# SAI_IO_BOTTOM_PCB_BOARD.net
KiCad netlist of a schematic drawn in EAGLE
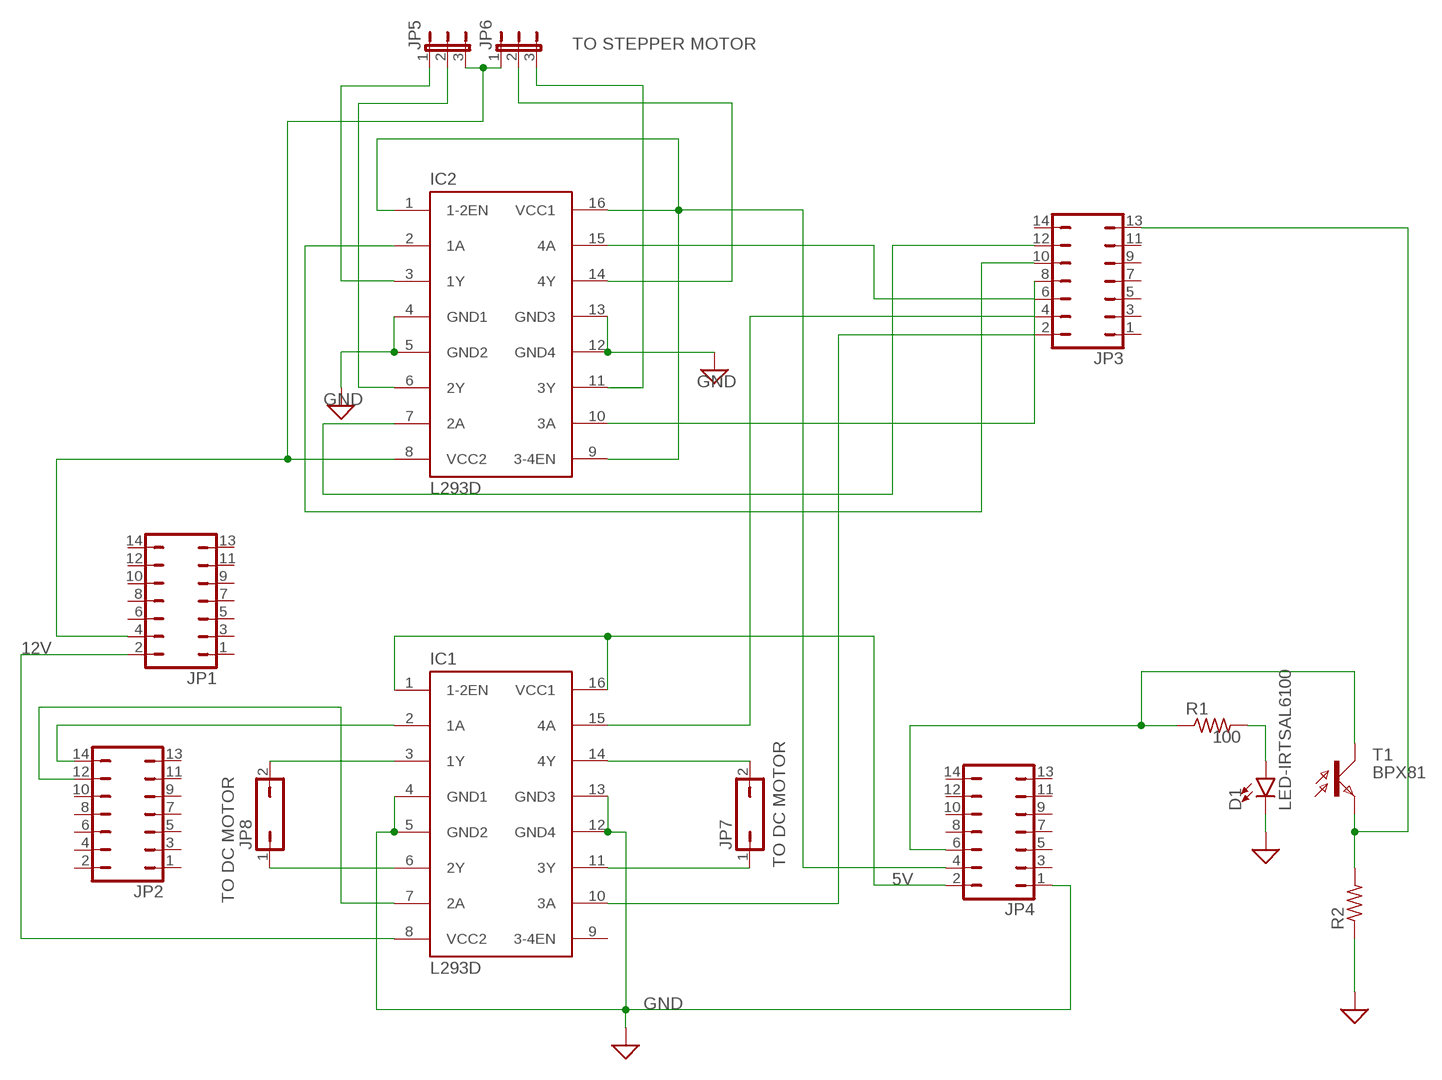
[diagram p0: schematic, sheet 1]

(export (version "E")
  (design (tool "Eeschema 10.0.6"))
  (components
    (comp (ref "D1")
      (value "LED-IRTSAL6100")
      (footprint "eagle-import:LED_5MM")
      (libsource (lib "eagle-import") (part "LED-IRTSAL6100"))
    )
    (comp (ref "IC1")
      (value "L293D")
      (footprint "eagle-import:DIL16")
      (libsource (lib "eagle-import") (part "L293D"))
    )
    (comp (ref "IC2")
      (value "L293D")
      (footprint "eagle-import:DIL16")
      (libsource (lib "eagle-import") (part "L293D"))
    )
    (comp (ref "JP1")
      (value "JP7Q")
      (footprint "eagle-import:JP7Q")
      (libsource (lib "eagle-import") (part "JP7Q"))
    )
    (comp (ref "JP2")
      (value "JP7Q")
      (footprint "eagle-import:JP7Q")
      (libsource (lib "eagle-import") (part "JP7Q"))
    )
    (comp (ref "JP3")
      (value "JP7Q")
      (footprint "eagle-import:JP7Q")
      (libsource (lib "eagle-import") (part "JP7Q"))
    )
    (comp (ref "JP4")
      (value "JP7Q")
      (footprint "eagle-import:JP7Q")
      (libsource (lib "eagle-import") (part "JP7Q"))
    )
    (comp (ref "JP5")
      (value "JP2E")
      (footprint "eagle-import:JP2")
      (libsource (lib "eagle-import") (part "JP2E"))
    )
    (comp (ref "JP6")
      (value "JP2E")
      (footprint "eagle-import:JP2")
      (libsource (lib "eagle-import") (part "JP2E"))
    )
    (comp (ref "JP7")
      (value "JP1Q")
      (footprint "eagle-import:JP1")
      (libsource (lib "eagle-import") (part "JP1Q"))
    )
    (comp (ref "JP8")
      (value "JP1Q")
      (footprint "eagle-import:JP1")
      (libsource (lib "eagle-import") (part "JP1Q"))
    )
    (comp (ref "R1")
      (value "R-US_0204/2V")
      (footprint "eagle-import:0204V")
      (libsource (lib "eagle-import") (part "R-US_0204/2V"))
    )
    (comp (ref "R2")
      (value "R-US_0204/2V")
      (footprint "eagle-import:0204V")
      (libsource (lib "eagle-import") (part "R-US_0204/2V"))
    )
    (comp (ref "T1")
      (value "BPX81")
      (footprint "eagle-import:BPX81")
      (libsource (lib "eagle-import") (part "BPX81"))
    )
  )
  (nets
    (net (code "1") (name "/5V") (class "Default")
      (node (ref "IC1") (pin "8") (pinfunction "VCC2_8") (pintype "power_in"))
      (node (ref "JP1") (pin "2") (pinfunction "2_2") (pintype "passive"))
    )
    (net (code "2") (name "Net-(D1-PadA)") (class "Default")
      (node (ref "D1") (pin "A") (pinfunction "A_A") (pintype "passive"))
      (node (ref "R1") (pin "2") (pinfunction "2_2") (pintype "passive"))
    )
    (net (code "3") (name "Net-(IC1-1-2EN)") (class "Default")
      (node (ref "IC1") (pin "1") (pinfunction "1-2EN_1") (pintype "input"))
      (node (ref "IC1") (pin "16") (pinfunction "VCC1_16") (pintype "power_in"))
      (node (ref "JP4") (pin "2") (pinfunction "2_2") (pintype "passive"))
    )
    (net (code "4") (name "Net-(IC1-1A)") (class "Default")
      (node (ref "IC1") (pin "2") (pinfunction "1A_2") (pintype "input"))
      (node (ref "JP2") (pin "14") (pinfunction "14_14") (pintype "passive"))
    )
    (net (code "5") (name "Net-(IC1-1Y)") (class "Default")
      (node (ref "IC1") (pin "3") (pinfunction "1Y_3") (pintype "output"))
      (node (ref "JP8") (pin "2") (pinfunction "2_2") (pintype "passive"))
    )
    (net (code "6") (name "Net-(IC1-2A)") (class "Default")
      (node (ref "IC1") (pin "7") (pinfunction "2A_7") (pintype "input"))
      (node (ref "JP2") (pin "12") (pinfunction "12_12") (pintype "passive"))
    )
    (net (code "7") (name "Net-(IC1-2Y)") (class "Default")
      (node (ref "IC1") (pin "6") (pinfunction "2Y_6") (pintype "output"))
      (node (ref "JP8") (pin "1") (pinfunction "1_1") (pintype "passive"))
    )
    (net (code "8") (name "Net-(IC1-3A)") (class "Default")
      (node (ref "IC1") (pin "10") (pinfunction "3A_10") (pintype "input"))
      (node (ref "JP3") (pin "2") (pinfunction "2_2") (pintype "passive"))
    )
    (net (code "9") (name "Net-(IC1-3Y)") (class "Default")
      (node (ref "IC1") (pin "11") (pinfunction "3Y_11") (pintype "output"))
      (node (ref "JP7") (pin "1") (pinfunction "1_1") (pintype "passive"))
    )
    (net (code "10") (name "Net-(IC1-4A)") (class "Default")
      (node (ref "IC1") (pin "15") (pinfunction "4A_15") (pintype "input"))
      (node (ref "JP3") (pin "4") (pinfunction "4_4") (pintype "passive"))
    )
    (net (code "11") (name "Net-(IC1-4Y)") (class "Default")
      (node (ref "IC1") (pin "14") (pinfunction "4Y_14") (pintype "output"))
      (node (ref "JP7") (pin "2") (pinfunction "2_2") (pintype "passive"))
    )
    (net (code "12") (name "Net-(IC2-1-2EN)") (class "Default")
      (node (ref "IC2") (pin "1") (pinfunction "1-2EN_1") (pintype "input"))
      (node (ref "IC2") (pin "16") (pinfunction "VCC1_16") (pintype "power_in"))
      (node (ref "IC2") (pin "9") (pinfunction "3-4EN_9") (pintype "input"))
      (node (ref "JP4") (pin "4") (pinfunction "4_4") (pintype "passive"))
    )
    (net (code "13") (name "Net-(IC2-1A)") (class "Default")
      (node (ref "IC2") (pin "2") (pinfunction "1A_2") (pintype "input"))
      (node (ref "JP3") (pin "10") (pinfunction "10_10") (pintype "passive"))
    )
    (net (code "14") (name "Net-(IC2-1Y)") (class "Default")
      (node (ref "IC2") (pin "3") (pinfunction "1Y_3") (pintype "output"))
      (node (ref "JP5") (pin "1") (pinfunction "1_1") (pintype "passive"))
    )
    (net (code "15") (name "Net-(IC2-2A)") (class "Default")
      (node (ref "IC2") (pin "7") (pinfunction "2A_7") (pintype "input"))
      (node (ref "JP3") (pin "12") (pinfunction "12_12") (pintype "passive"))
    )
    (net (code "16") (name "Net-(IC2-2Y)") (class "Default")
      (node (ref "IC2") (pin "6") (pinfunction "2Y_6") (pintype "output"))
      (node (ref "JP5") (pin "2") (pinfunction "2_2") (pintype "passive"))
    )
    (net (code "17") (name "Net-(IC2-3A)") (class "Default")
      (node (ref "IC2") (pin "10") (pinfunction "3A_10") (pintype "input"))
      (node (ref "JP3") (pin "8") (pinfunction "8_8") (pintype "passive"))
    )
    (net (code "18") (name "Net-(IC2-3Y)") (class "Default")
      (node (ref "IC2") (pin "11") (pinfunction "3Y_11") (pintype "output"))
      (node (ref "JP6") (pin "3") (pinfunction "3_3") (pintype "passive"))
    )
    (net (code "19") (name "Net-(IC2-4A)") (class "Default")
      (node (ref "IC2") (pin "15") (pinfunction "4A_15") (pintype "input"))
      (node (ref "JP3") (pin "6") (pinfunction "6_6") (pintype "passive"))
    )
    (net (code "20") (name "Net-(IC2-4Y)") (class "Default")
      (node (ref "IC2") (pin "14") (pinfunction "4Y_14") (pintype "output"))
      (node (ref "JP6") (pin "2") (pinfunction "2_2") (pintype "passive"))
    )
    (net (code "21") (name "Net-(IC2-VCC2)") (class "Default")
      (node (ref "IC2") (pin "8") (pinfunction "VCC2_8") (pintype "power_in"))
      (node (ref "JP1") (pin "4") (pinfunction "4_4") (pintype "passive"))
      (node (ref "JP5") (pin "3") (pinfunction "3_3") (pintype "passive"))
      (node (ref "JP6") (pin "1") (pinfunction "1_1") (pintype "passive"))
    )
    (net (code "22") (name "Net-(JP3-Pad13)") (class "Default")
      (node (ref "JP3") (pin "13") (pinfunction "13_13") (pintype "passive"))
      (node (ref "R2") (pin "2") (pinfunction "2_2") (pintype "passive"))
      (node (ref "T1") (pin "E") (pinfunction "E_E") (pintype "passive"))
    )
    (net (code "23") (name "Net-(JP4-Pad6)") (class "Default")
      (node (ref "JP4") (pin "6") (pinfunction "6_6") (pintype "passive"))
      (node (ref "R1") (pin "1") (pinfunction "1_1") (pintype "passive"))
      (node (ref "T1") (pin "C") (pinfunction "C_C") (pintype "passive"))
    )
    (net (code "24") (name "SUP") (class "Default")
      (node (ref "D1") (pin "K") (pinfunction "C_K") (pintype "passive"))
      (node (ref "IC1") (pin "12") (pinfunction "GND4_12") (pintype "power_in"))
      (node (ref "IC1") (pin "13") (pinfunction "GND3_13") (pintype "power_in"))
      (node (ref "IC1") (pin "4") (pinfunction "GND1_4") (pintype "power_in"))
      (node (ref "IC1") (pin "5") (pinfunction "GND2_5") (pintype "power_in"))
      (node (ref "IC2") (pin "12") (pinfunction "GND4_12") (pintype "power_in"))
      (node (ref "IC2") (pin "13") (pinfunction "GND3_13") (pintype "power_in"))
      (node (ref "IC2") (pin "4") (pinfunction "GND1_4") (pintype "power_in"))
      (node (ref "IC2") (pin "5") (pinfunction "GND2_5") (pintype "power_in"))
      (node (ref "JP4") (pin "1") (pinfunction "1_1") (pintype "passive"))
      (node (ref "R2") (pin "1") (pinfunction "1_1") (pintype "passive"))
    )
    (net (code "25") (name "unconnected-(IC1-3-4EN-Pad9)") (class "Default")
      (node (ref "IC1") (pin "9") (pinfunction "3-4EN_9") (pintype "input"))
    )
    (net (code "26") (name "unconnected-(JP1-Pad1)") (class "Default")
      (node (ref "JP1") (pin "1") (pinfunction "1_1") (pintype "passive"))
    )
    (net (code "27") (name "unconnected-(JP1-Pad3)") (class "Default")
      (node (ref "JP1") (pin "3") (pinfunction "3_3") (pintype "passive"))
    )
    (net (code "28") (name "unconnected-(JP1-Pad5)") (class "Default")
      (node (ref "JP1") (pin "5") (pinfunction "5_5") (pintype "passive"))
    )
    (net (code "29") (name "unconnected-(JP1-Pad6)") (class "Default")
      (node (ref "JP1") (pin "6") (pinfunction "6_6") (pintype "passive"))
    )
    (net (code "30") (name "unconnected-(JP1-Pad7)") (class "Default")
      (node (ref "JP1") (pin "7") (pinfunction "7_7") (pintype "passive"))
    )
    (net (code "31") (name "unconnected-(JP1-Pad8)") (class "Default")
      (node (ref "JP1") (pin "8") (pinfunction "8_8") (pintype "passive"))
    )
    (net (code "32") (name "unconnected-(JP1-Pad9)") (class "Default")
      (node (ref "JP1") (pin "9") (pinfunction "9_9") (pintype "passive"))
    )
    (net (code "33") (name "unconnected-(JP1-Pad10)") (class "Default")
      (node (ref "JP1") (pin "10") (pinfunction "10_10") (pintype "passive"))
    )
    (net (code "34") (name "unconnected-(JP1-Pad11)") (class "Default")
      (node (ref "JP1") (pin "11") (pinfunction "11_11") (pintype "passive"))
    )
    (net (code "35") (name "unconnected-(JP1-Pad12)") (class "Default")
      (node (ref "JP1") (pin "12") (pinfunction "12_12") (pintype "passive"))
    )
    (net (code "36") (name "unconnected-(JP1-Pad13)") (class "Default")
      (node (ref "JP1") (pin "13") (pinfunction "13_13") (pintype "passive"))
    )
    (net (code "37") (name "unconnected-(JP1-Pad14)") (class "Default")
      (node (ref "JP1") (pin "14") (pinfunction "14_14") (pintype "passive"))
    )
    (net (code "38") (name "unconnected-(JP2-Pad1)") (class "Default")
      (node (ref "JP2") (pin "1") (pinfunction "1_1") (pintype "passive"))
    )
    (net (code "39") (name "unconnected-(JP2-Pad2)") (class "Default")
      (node (ref "JP2") (pin "2") (pinfunction "2_2") (pintype "passive"))
    )
    (net (code "40") (name "unconnected-(JP2-Pad3)") (class "Default")
      (node (ref "JP2") (pin "3") (pinfunction "3_3") (pintype "passive"))
    )
    (net (code "41") (name "unconnected-(JP2-Pad4)") (class "Default")
      (node (ref "JP2") (pin "4") (pinfunction "4_4") (pintype "passive"))
    )
    (net (code "42") (name "unconnected-(JP2-Pad5)") (class "Default")
      (node (ref "JP2") (pin "5") (pinfunction "5_5") (pintype "passive"))
    )
    (net (code "43") (name "unconnected-(JP2-Pad6)") (class "Default")
      (node (ref "JP2") (pin "6") (pinfunction "6_6") (pintype "passive"))
    )
    (net (code "44") (name "unconnected-(JP2-Pad7)") (class "Default")
      (node (ref "JP2") (pin "7") (pinfunction "7_7") (pintype "passive"))
    )
    (net (code "45") (name "unconnected-(JP2-Pad8)") (class "Default")
      (node (ref "JP2") (pin "8") (pinfunction "8_8") (pintype "passive"))
    )
    (net (code "46") (name "unconnected-(JP2-Pad9)") (class "Default")
      (node (ref "JP2") (pin "9") (pinfunction "9_9") (pintype "passive"))
    )
    (net (code "47") (name "unconnected-(JP2-Pad10)") (class "Default")
      (node (ref "JP2") (pin "10") (pinfunction "10_10") (pintype "passive"))
    )
    (net (code "48") (name "unconnected-(JP2-Pad11)") (class "Default")
      (node (ref "JP2") (pin "11") (pinfunction "11_11") (pintype "passive"))
    )
    (net (code "49") (name "unconnected-(JP2-Pad13)") (class "Default")
      (node (ref "JP2") (pin "13") (pinfunction "13_13") (pintype "passive"))
    )
    (net (code "50") (name "unconnected-(JP3-Pad1)") (class "Default")
      (node (ref "JP3") (pin "1") (pinfunction "1_1") (pintype "passive"))
    )
    (net (code "51") (name "unconnected-(JP3-Pad3)") (class "Default")
      (node (ref "JP3") (pin "3") (pinfunction "3_3") (pintype "passive"))
    )
    (net (code "52") (name "unconnected-(JP3-Pad5)") (class "Default")
      (node (ref "JP3") (pin "5") (pinfunction "5_5") (pintype "passive"))
    )
    (net (code "53") (name "unconnected-(JP3-Pad7)") (class "Default")
      (node (ref "JP3") (pin "7") (pinfunction "7_7") (pintype "passive"))
    )
    (net (code "54") (name "unconnected-(JP3-Pad9)") (class "Default")
      (node (ref "JP3") (pin "9") (pinfunction "9_9") (pintype "passive"))
    )
    (net (code "55") (name "unconnected-(JP3-Pad11)") (class "Default")
      (node (ref "JP3") (pin "11") (pinfunction "11_11") (pintype "passive"))
    )
    (net (code "56") (name "unconnected-(JP3-Pad14)") (class "Default")
      (node (ref "JP3") (pin "14") (pinfunction "14_14") (pintype "passive"))
    )
    (net (code "57") (name "unconnected-(JP4-Pad3)") (class "Default")
      (node (ref "JP4") (pin "3") (pinfunction "3_3") (pintype "passive"))
    )
    (net (code "58") (name "unconnected-(JP4-Pad5)") (class "Default")
      (node (ref "JP4") (pin "5") (pinfunction "5_5") (pintype "passive"))
    )
    (net (code "59") (name "unconnected-(JP4-Pad7)") (class "Default")
      (node (ref "JP4") (pin "7") (pinfunction "7_7") (pintype "passive"))
    )
    (net (code "60") (name "unconnected-(JP4-Pad8)") (class "Default")
      (node (ref "JP4") (pin "8") (pinfunction "8_8") (pintype "passive"))
    )
    (net (code "61") (name "unconnected-(JP4-Pad9)") (class "Default")
      (node (ref "JP4") (pin "9") (pinfunction "9_9") (pintype "passive"))
    )
    (net (code "62") (name "unconnected-(JP4-Pad10)") (class "Default")
      (node (ref "JP4") (pin "10") (pinfunction "10_10") (pintype "passive"))
    )
    (net (code "63") (name "unconnected-(JP4-Pad11)") (class "Default")
      (node (ref "JP4") (pin "11") (pinfunction "11_11") (pintype "passive"))
    )
    (net (code "64") (name "unconnected-(JP4-Pad12)") (class "Default")
      (node (ref "JP4") (pin "12") (pinfunction "12_12") (pintype "passive"))
    )
    (net (code "65") (name "unconnected-(JP4-Pad13)") (class "Default")
      (node (ref "JP4") (pin "13") (pinfunction "13_13") (pintype "passive"))
    )
    (net (code "66") (name "unconnected-(JP4-Pad14)") (class "Default")
      (node (ref "JP4") (pin "14") (pinfunction "14_14") (pintype "passive"))
    )
  )
)
